# Flex-It.net
KiCad netlist of a schematic drawn in EAGLE
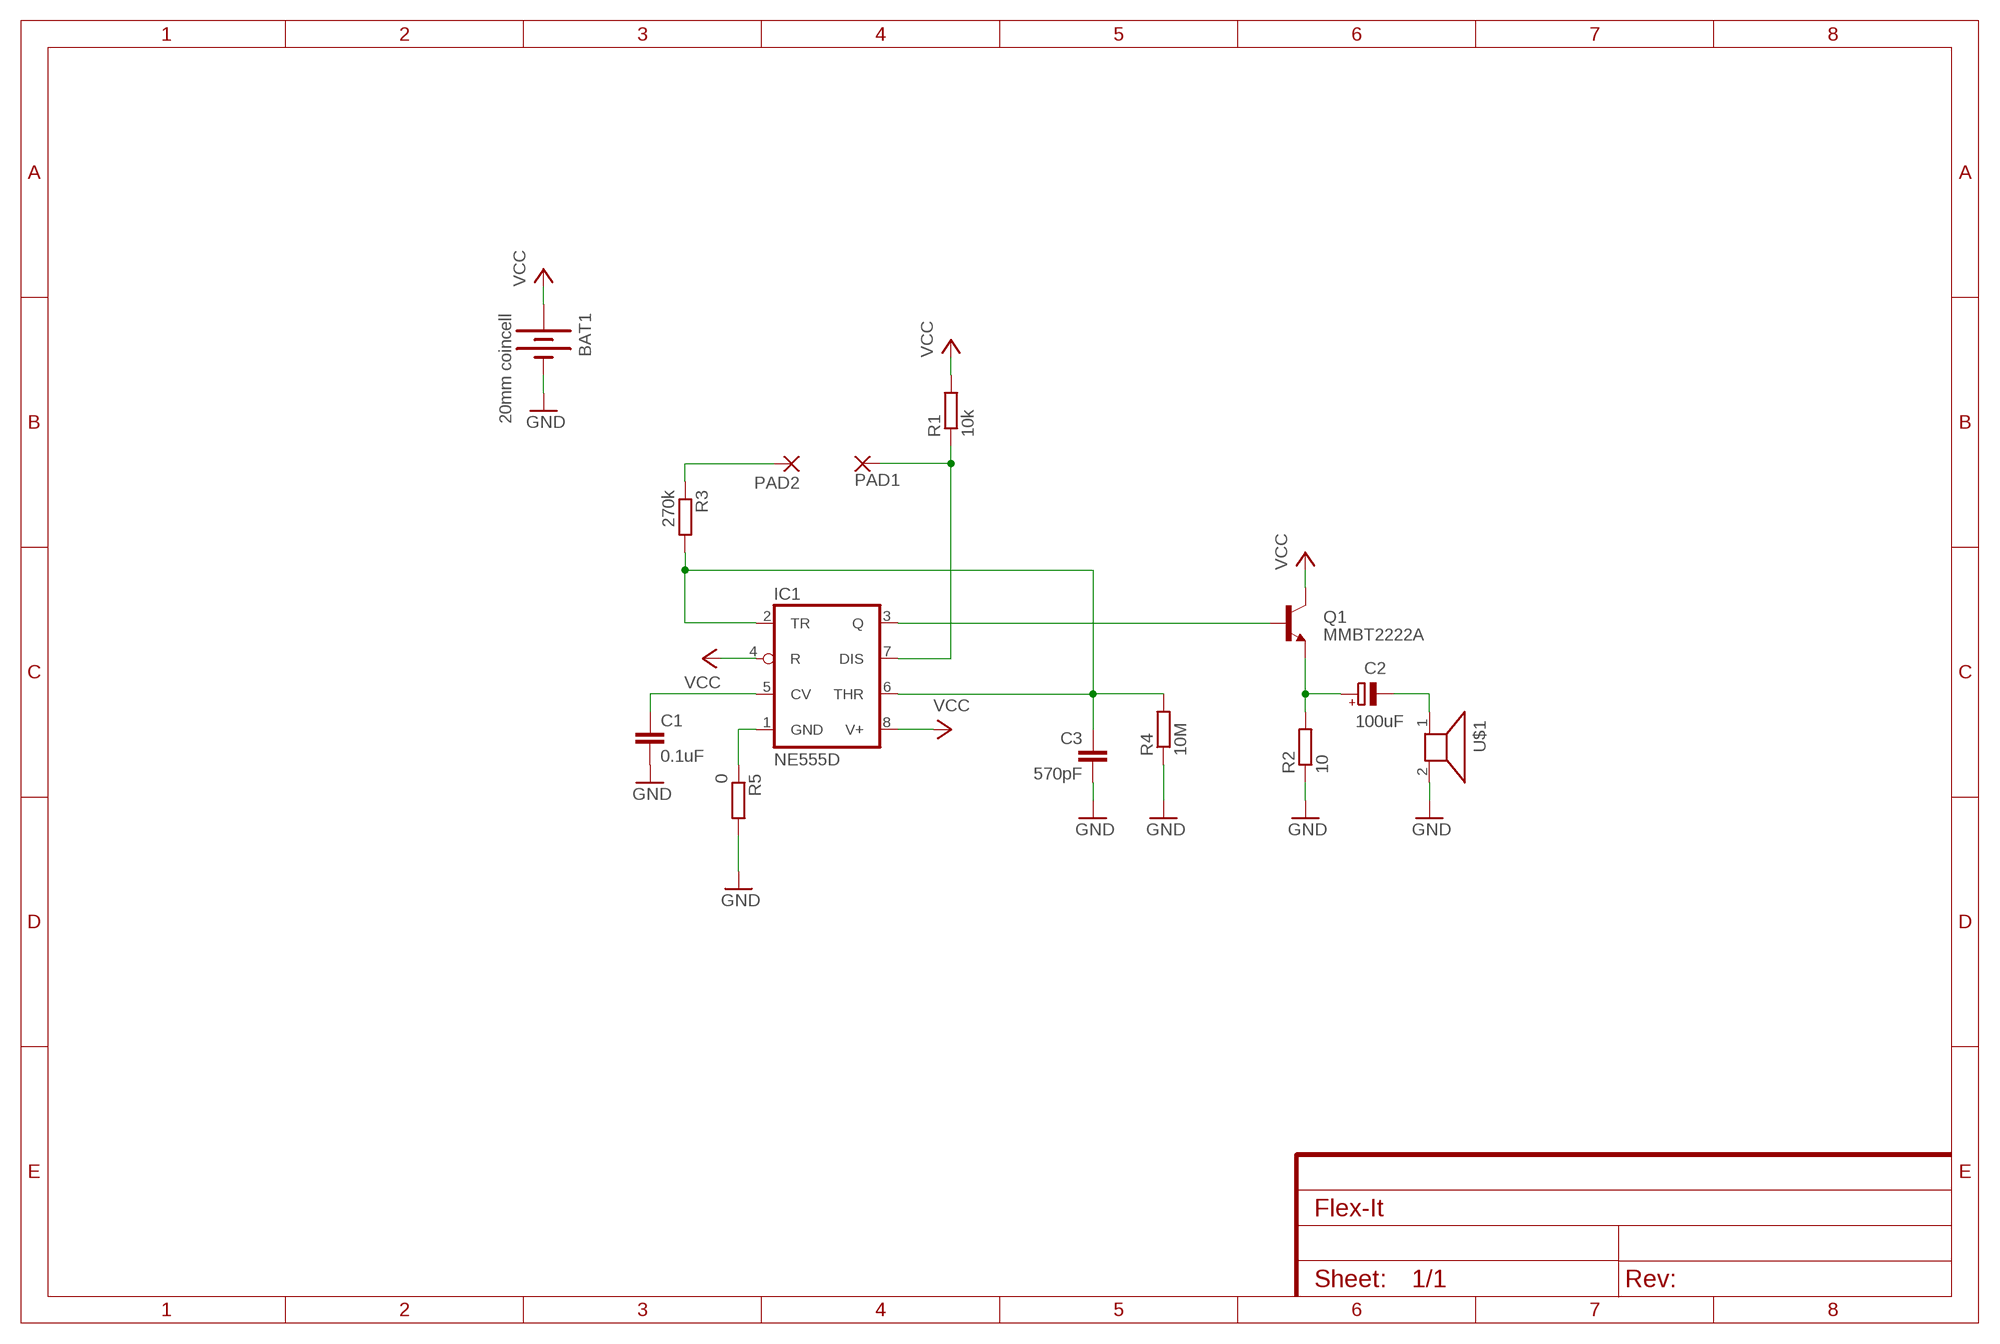
[diagram p0: schematic, sheet 1]

(export (version "E")
  (design (tool "Eeschema 10.0.6"))
  (components
    (comp (ref "BAT1")
      (value "20mm coincell")
      (footprint "eagle-import:BATTCON_20MM_4LEGS")
      (libsource (lib "eagle-import") (part "BATTERY20MM_4LEGS"))
    )
    (comp (ref "C1")
      (value "0.1uF")
      (footprint "eagle-import:C1206K")
      (libsource (lib "eagle-import") (part "C-EUC1206K"))
    )
    (comp (ref "C2")
      (value "100uF")
      (footprint "eagle-import:SMC_B")
      (libsource (lib "eagle-import") (part "CPOL-EUSMCB"))
    )
    (comp (ref "C3")
      (value "570pF")
      (footprint "eagle-import:C1206K")
      (libsource (lib "eagle-import") (part "C-EUC1206K"))
    )
    (comp (ref "IC1")
      (value "NE555D")
      (footprint "eagle-import:SO08")
      (libsource (lib "eagle-import") (part "555DNE"))
    )
    (comp (ref "PAD1")
      (value "WIREPADSMD1,27-254")
      (footprint "eagle-import:SMD1,27-2,54")
      (libsource (lib "eagle-import") (part "WIREPADSMD1,27-254"))
    )
    (comp (ref "PAD2")
      (value "WIREPADSMD1,27-254")
      (footprint "eagle-import:SMD1,27-2,54")
      (libsource (lib "eagle-import") (part "WIREPADSMD1,27-254"))
    )
    (comp (ref "Q1")
      (value "MMBT2222A")
      (footprint "eagle-import:SOT23-3")
      (libsource (lib "eagle-import") (part "TRANSISTOR_NPNMMBT2222A"))
    )
    (comp (ref "R1")
      (value "10k")
      (footprint "eagle-import:R1206")
      (libsource (lib "eagle-import") (part "R-EU_R1206"))
    )
    (comp (ref "R2")
      (value "10")
      (footprint "eagle-import:R1206")
      (libsource (lib "eagle-import") (part "R-EU_R1206"))
    )
    (comp (ref "R3")
      (value "270k")
      (footprint "eagle-import:R1206")
      (libsource (lib "eagle-import") (part "R-EU_R1206"))
    )
    (comp (ref "R4")
      (value "10M")
      (footprint "eagle-import:R1206")
      (libsource (lib "eagle-import") (part "R-EU_R1206"))
    )
    (comp (ref "R5")
      (value "0")
      (footprint "eagle-import:R1206")
      (libsource (lib "eagle-import") (part "R-EU_R1206"))
    )
    (comp (ref "U$1")
      (value "PS603SPK")
      (footprint "eagle-import:PS603")
      (libsource (lib "eagle-import") (part "PS603SPK"))
    )
  )
  (nets
    (net (code "1") (name "GND") (class "Default")
      (node (ref "BAT1") (pin "2") (pinfunction "-_2") (pintype "power_in"))
      (node (ref "C1") (pin "2") (pinfunction "2_2") (pintype "passive"))
      (node (ref "C3") (pin "2") (pinfunction "2_2") (pintype "passive"))
      (node (ref "IC1") (pin "1") (pinfunction "GND_1") (pintype "power_in"))
      (node (ref "R2") (pin "1") (pinfunction "1_1") (pintype "passive"))
      (node (ref "R4") (pin "1") (pinfunction "1_1") (pintype "passive"))
      (node (ref "R5") (pin "1") (pinfunction "1_1") (pintype "passive"))
      (node (ref "R5") (pin "2") (pinfunction "2_2") (pintype "passive"))
      (node (ref "U$1") (pin "2") (pinfunction "2_2") (pintype "passive"))
    )
    (net (code "2") (name "Net-(C2-Pad-)") (class "Default")
      (node (ref "C2") (pin "-") (pinfunction "-_-") (pintype "passive"))
      (node (ref "U$1") (pin "1") (pinfunction "1_1") (pintype "passive"))
    )
    (net (code "3") (name "Net-(IC1-CV)") (class "Default")
      (node (ref "C1") (pin "1") (pinfunction "1_1") (pintype "passive"))
      (node (ref "IC1") (pin "5") (pinfunction "CV_5") (pintype "input"))
    )
    (net (code "4") (name "Net-(IC1-DIS)") (class "Default")
      (node (ref "IC1") (pin "7") (pinfunction "DIS_7") (pintype "input"))
      (node (ref "PAD1") (pin "1") (pinfunction "P_1") (pintype "passive"))
      (node (ref "R1") (pin "1") (pinfunction "1_1") (pintype "passive"))
    )
    (net (code "5") (name "Net-(IC1-Q)") (class "Default")
      (node (ref "IC1") (pin "3") (pinfunction "Q_3") (pintype "output"))
      (node (ref "Q1") (pin "1") (pinfunction "B_1") (pintype "passive"))
    )
    (net (code "6") (name "Net-(IC1-THR)") (class "Default")
      (node (ref "C3") (pin "1") (pinfunction "1_1") (pintype "passive"))
      (node (ref "IC1") (pin "2") (pinfunction "TR_2") (pintype "input"))
      (node (ref "IC1") (pin "6") (pinfunction "THR_6") (pintype "input"))
      (node (ref "R3") (pin "2") (pinfunction "2_2") (pintype "passive"))
      (node (ref "R4") (pin "2") (pinfunction "2_2") (pintype "passive"))
    )
    (net (code "7") (name "Net-(PAD2-P)") (class "Default")
      (node (ref "PAD2") (pin "1") (pinfunction "P_1") (pintype "passive"))
      (node (ref "R3") (pin "1") (pinfunction "1_1") (pintype "passive"))
    )
    (net (code "8") (name "Net-(Q1-E)") (class "Default")
      (node (ref "C2") (pin "+") (pinfunction "+_+") (pintype "passive"))
      (node (ref "Q1") (pin "2") (pinfunction "E_2") (pintype "passive"))
      (node (ref "R2") (pin "2") (pinfunction "2_2") (pintype "passive"))
    )
    (net (code "9") (name "VCC") (class "Default")
      (node (ref "BAT1") (pin "1") (pinfunction "+_1") (pintype "power_in"))
      (node (ref "BAT1") (pin "3") (pinfunction "+_3") (pintype "power_in"))
      (node (ref "BAT1") (pin "P$1") (pinfunction "+_P$1") (pintype "power_in"))
      (node (ref "BAT1") (pin "P$2") (pinfunction "+_P$2") (pintype "power_in"))
      (node (ref "IC1") (pin "4") (pinfunction "R_4") (pintype "input"))
      (node (ref "IC1") (pin "8") (pinfunction "V+_8") (pintype "power_in"))
      (node (ref "Q1") (pin "3") (pinfunction "C_3") (pintype "passive"))
      (node (ref "R1") (pin "2") (pinfunction "2_2") (pintype "passive"))
    )
  )
)
